# mcb-enhancer-v1.net
KiCad netlist of a schematic drawn in EAGLE
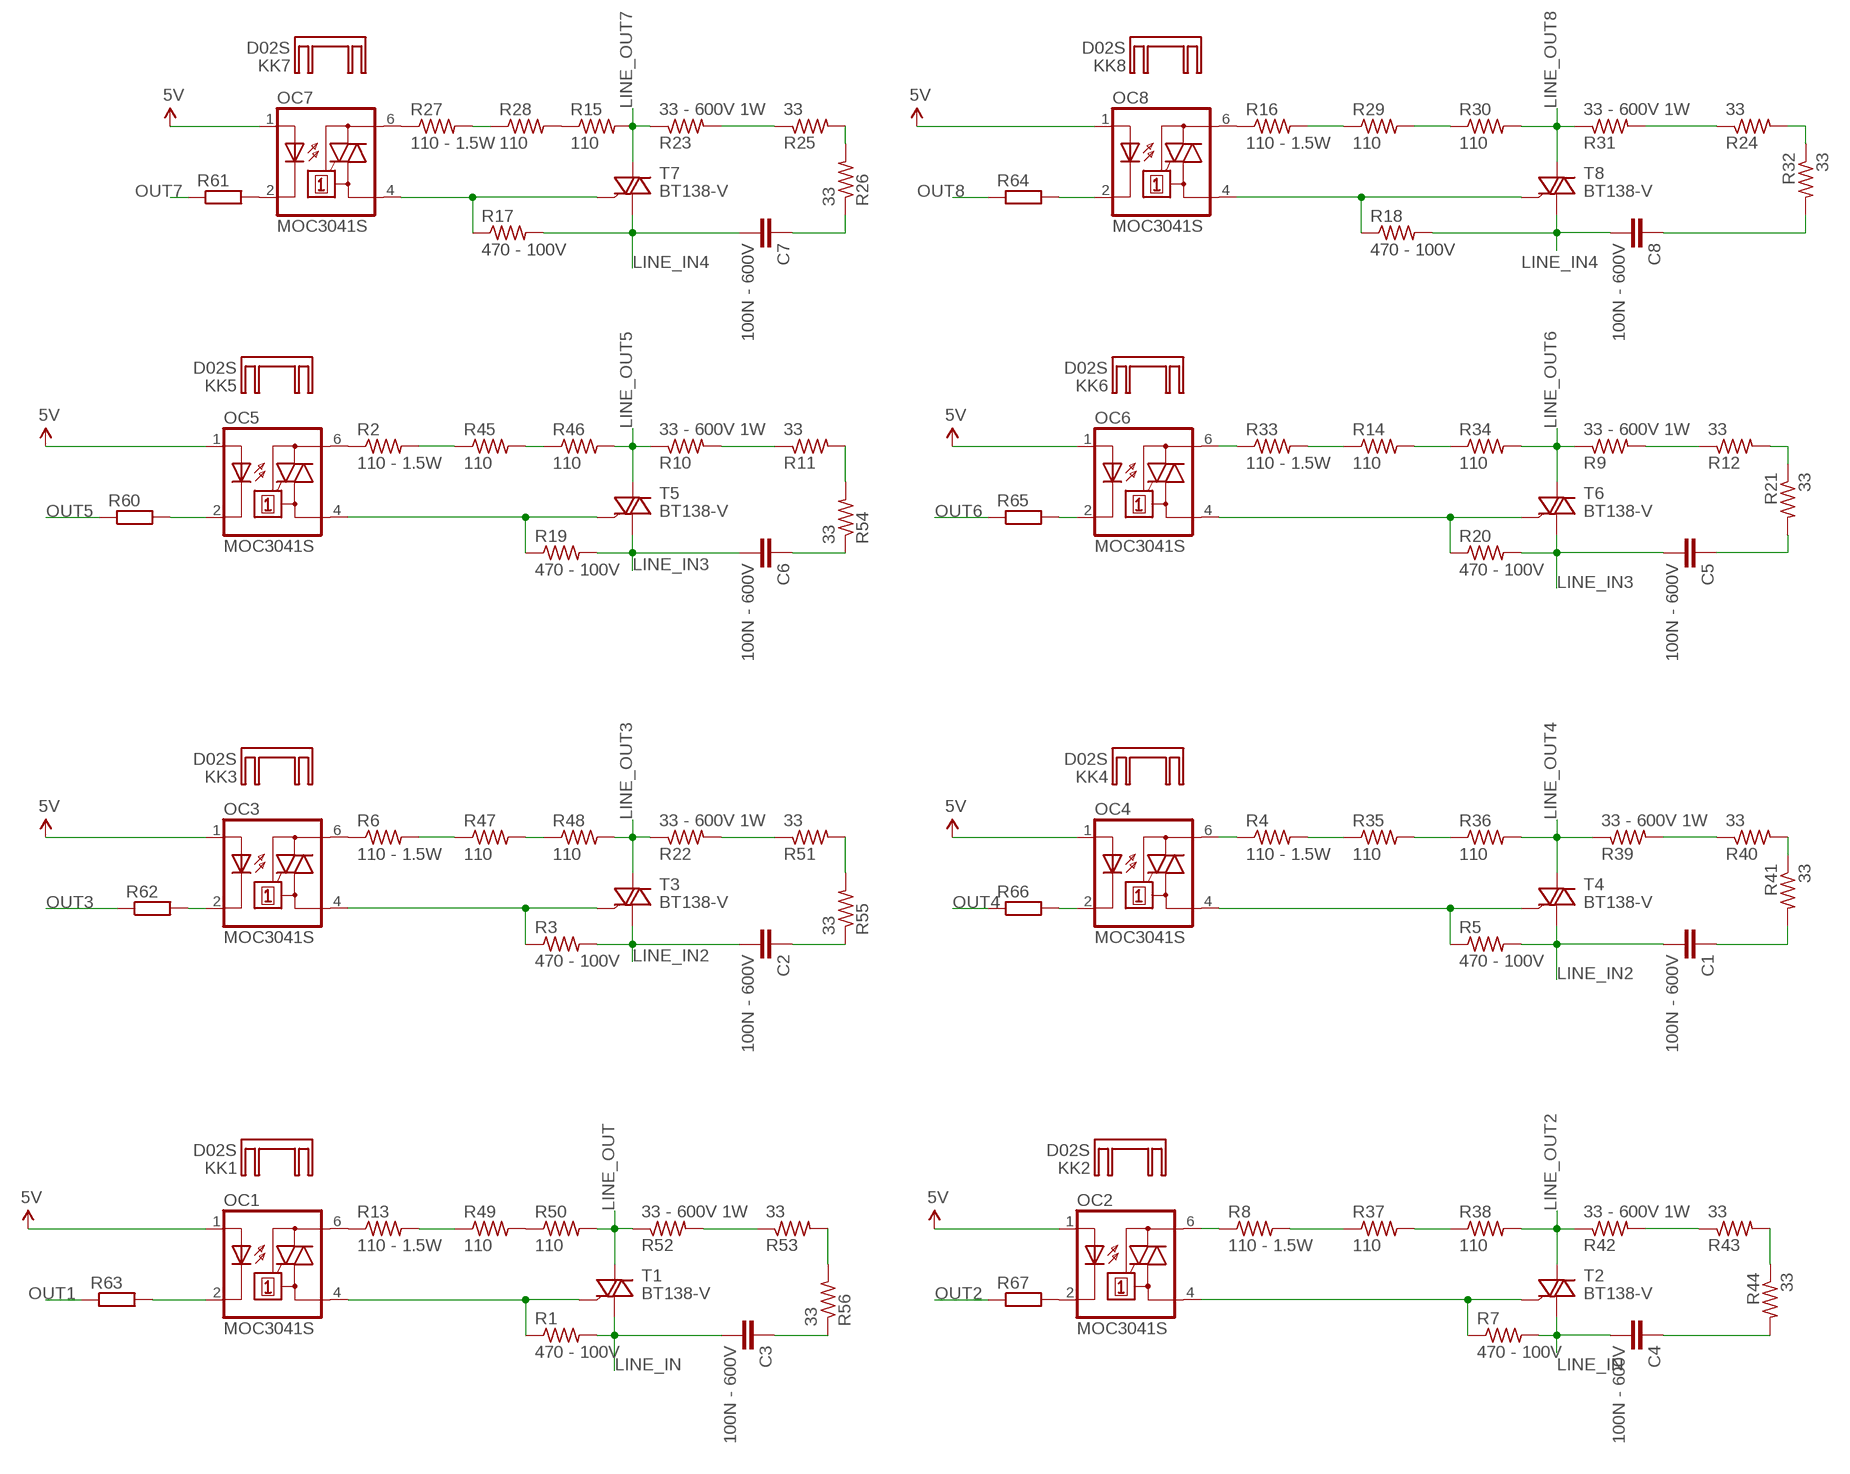
[diagram p0: schematic, sheet 1]

(export (version "E")
  (design (tool "Eeschema 10.0.6"))
  (components
    (comp (ref "C1")
      (value "100N - 600V")
      (footprint "eagle-import:C050-030X075")
      (libsource (lib "eagle-import") (part "C-EU050-030X075"))
    )
    (comp (ref "C2")
      (value "100N - 600V")
      (footprint "eagle-import:C050-030X075")
      (libsource (lib "eagle-import") (part "C-EU050-030X075"))
    )
    (comp (ref "C3")
      (value "100N - 600V")
      (footprint "eagle-import:C050-030X075")
      (libsource (lib "eagle-import") (part "C-EU050-030X075"))
    )
    (comp (ref "C4")
      (value "100N - 600V")
      (footprint "eagle-import:C050-030X075")
      (libsource (lib "eagle-import") (part "C-EU050-030X075"))
    )
    (comp (ref "C5")
      (value "100N - 600V")
      (footprint "eagle-import:C050-030X075")
      (libsource (lib "eagle-import") (part "C-EU050-030X075"))
    )
    (comp (ref "C6")
      (value "100N - 600V")
      (footprint "eagle-import:C050-030X075")
      (libsource (lib "eagle-import") (part "C-EU050-030X075"))
    )
    (comp (ref "C7")
      (value "100N - 600V")
      (footprint "eagle-import:C050-030X075")
      (libsource (lib "eagle-import") (part "C-EU050-030X075"))
    )
    (comp (ref "C8")
      (value "100N - 600V")
      (footprint "eagle-import:C050-030X075")
      (libsource (lib "eagle-import") (part "C-EU050-030X075"))
    )
    (comp (ref "KK1")
      (value "D02S")
      (footprint "eagle-import:D02S")
      (libsource (lib "eagle-import") (part "D02S"))
    )
    (comp (ref "KK2")
      (value "D02S")
      (footprint "eagle-import:D02S")
      (libsource (lib "eagle-import") (part "D02S"))
    )
    (comp (ref "KK3")
      (value "D02S")
      (footprint "eagle-import:D02S")
      (libsource (lib "eagle-import") (part "D02S"))
    )
    (comp (ref "KK4")
      (value "D02S")
      (footprint "eagle-import:D02S")
      (libsource (lib "eagle-import") (part "D02S"))
    )
    (comp (ref "KK5")
      (value "D02S")
      (footprint "eagle-import:D02S")
      (libsource (lib "eagle-import") (part "D02S"))
    )
    (comp (ref "KK6")
      (value "D02S")
      (footprint "eagle-import:D02S")
      (libsource (lib "eagle-import") (part "D02S"))
    )
    (comp (ref "KK7")
      (value "D02S")
      (footprint "eagle-import:D02S")
      (libsource (lib "eagle-import") (part "D02S"))
    )
    (comp (ref "KK8")
      (value "D02S")
      (footprint "eagle-import:D02S")
      (libsource (lib "eagle-import") (part "D02S"))
    )
    (comp (ref "OC1")
      (value "MOC3041S")
      (footprint "eagle-import:DIL6-SMD")
      (fields
        (field (name "MF") "FAIRCHILD SEMICONDUCTOR")
        (field (name "MPN") "MOC3041S-M")
        (field (name "MPN_1") "MOC3033S-M")
        (field (name "OC_FARNELL") "unknown")
        (field (name "OC_NEWARK") "05C2878")
      )
      (libsource (lib "eagle-import") (part "MOC30S41"))
    )
    (comp (ref "OC2")
      (value "MOC3041S")
      (footprint "eagle-import:DIL6-SMD")
      (fields
        (field (name "MF") "FAIRCHILD SEMICONDUCTOR")
        (field (name "MPN") "MOC3041S-M")
        (field (name "MPN_1") "MOC3033S-M")
        (field (name "OC_FARNELL") "unknown")
        (field (name "OC_NEWARK") "05C2878")
      )
      (libsource (lib "eagle-import") (part "MOC30S41"))
    )
    (comp (ref "OC3")
      (value "MOC3041S")
      (footprint "eagle-import:DIL6-SMD")
      (fields
        (field (name "MF") "FAIRCHILD SEMICONDUCTOR")
        (field (name "MPN") "MOC3041S-M")
        (field (name "MPN_1") "MOC3033S-M")
        (field (name "OC_FARNELL") "unknown")
        (field (name "OC_NEWARK") "05C2878")
      )
      (libsource (lib "eagle-import") (part "MOC30S41"))
    )
    (comp (ref "OC4")
      (value "MOC3041S")
      (footprint "eagle-import:DIL6-SMD")
      (fields
        (field (name "MF") "FAIRCHILD SEMICONDUCTOR")
        (field (name "MPN") "MOC3041S-M")
        (field (name "MPN_1") "MOC3033S-M")
        (field (name "OC_FARNELL") "unknown")
        (field (name "OC_NEWARK") "05C2878")
      )
      (libsource (lib "eagle-import") (part "MOC30S41"))
    )
    (comp (ref "OC5")
      (value "MOC3041S")
      (footprint "eagle-import:DIL6-SMD")
      (fields
        (field (name "MF") "FAIRCHILD SEMICONDUCTOR")
        (field (name "MPN") "MOC3041S-M")
        (field (name "MPN_1") "MOC3033S-M")
        (field (name "OC_FARNELL") "unknown")
        (field (name "OC_NEWARK") "05C2878")
      )
      (libsource (lib "eagle-import") (part "MOC30S41"))
    )
    (comp (ref "OC6")
      (value "MOC3041S")
      (footprint "eagle-import:DIL6-SMD")
      (fields
        (field (name "MF") "FAIRCHILD SEMICONDUCTOR")
        (field (name "MPN") "MOC3041S-M")
        (field (name "MPN_1") "MOC3033S-M")
        (field (name "OC_FARNELL") "unknown")
        (field (name "OC_NEWARK") "05C2878")
      )
      (libsource (lib "eagle-import") (part "MOC30S41"))
    )
    (comp (ref "OC7")
      (value "MOC3041S")
      (footprint "eagle-import:DIL6-SMD")
      (fields
        (field (name "MF") "FAIRCHILD SEMICONDUCTOR")
        (field (name "MPN") "MOC3041S-M")
        (field (name "MPN_1") "MOC3033S-M")
        (field (name "OC_FARNELL") "unknown")
        (field (name "OC_NEWARK") "05C2878")
      )
      (libsource (lib "eagle-import") (part "MOC30S41"))
    )
    (comp (ref "OC8")
      (value "MOC3041S")
      (footprint "eagle-import:DIL6-SMD")
      (fields
        (field (name "MF") "FAIRCHILD SEMICONDUCTOR")
        (field (name "MPN") "MOC3041S-M")
        (field (name "MPN_1") "MOC3033S-M")
        (field (name "OC_FARNELL") "unknown")
        (field (name "OC_NEWARK") "05C2878")
      )
      (libsource (lib "eagle-import") (part "MOC30S41"))
    )
    (comp (ref "R1")
      (value "470 - 100V")
      (footprint "eagle-import:M1206")
      (libsource (lib "eagle-import") (part "R-US_M1206"))
    )
    (comp (ref "R2")
      (value "110 - 1.5W")
      (footprint "eagle-import:R2512")
      (libsource (lib "eagle-import") (part "R-US_R2512"))
    )
    (comp (ref "R3")
      (value "470 - 100V")
      (footprint "eagle-import:M1206")
      (libsource (lib "eagle-import") (part "R-US_M1206"))
    )
    (comp (ref "R4")
      (value "110 - 1.5W")
      (footprint "eagle-import:R2512")
      (libsource (lib "eagle-import") (part "R-US_R2512"))
    )
    (comp (ref "R5")
      (value "470 - 100V")
      (footprint "eagle-import:M1206")
      (libsource (lib "eagle-import") (part "R-US_M1206"))
    )
    (comp (ref "R6")
      (value "110 - 1.5W")
      (footprint "eagle-import:R2512")
      (libsource (lib "eagle-import") (part "R-US_R2512"))
    )
    (comp (ref "R7")
      (value "470 - 100V")
      (footprint "eagle-import:M1206")
      (libsource (lib "eagle-import") (part "R-US_M1206"))
    )
    (comp (ref "R8")
      (value "110 - 1.5W")
      (footprint "eagle-import:R2512")
      (libsource (lib "eagle-import") (part "R-US_R2512"))
    )
    (comp (ref "R9")
      (value "33 - 600V 1W")
      (footprint "eagle-import:M1206")
      (libsource (lib "eagle-import") (part "R-US_M1206"))
    )
    (comp (ref "R10")
      (value "33 - 600V 1W")
      (footprint "eagle-import:M1206")
      (libsource (lib "eagle-import") (part "R-US_M1206"))
    )
    (comp (ref "R11")
      (value "33")
      (footprint "eagle-import:M1206")
      (libsource (lib "eagle-import") (part "R-US_M1206"))
    )
    (comp (ref "R12")
      (value "33")
      (footprint "eagle-import:M1206")
      (libsource (lib "eagle-import") (part "R-US_M1206"))
    )
    (comp (ref "R13")
      (value "110 - 1.5W")
      (footprint "eagle-import:R2512")
      (libsource (lib "eagle-import") (part "R-US_R2512"))
    )
    (comp (ref "R14")
      (value "110")
      (footprint "eagle-import:R2512")
      (libsource (lib "eagle-import") (part "R-US_R2512"))
    )
    (comp (ref "R15")
      (value "110")
      (footprint "eagle-import:R2512")
      (libsource (lib "eagle-import") (part "R-US_R2512"))
    )
    (comp (ref "R16")
      (value "110 - 1.5W")
      (footprint "eagle-import:R2512")
      (libsource (lib "eagle-import") (part "R-US_R2512"))
    )
    (comp (ref "R17")
      (value "470 - 100V")
      (footprint "eagle-import:M1206")
      (libsource (lib "eagle-import") (part "R-US_M1206"))
    )
    (comp (ref "R18")
      (value "470 - 100V")
      (footprint "eagle-import:M1206")
      (libsource (lib "eagle-import") (part "R-US_M1206"))
    )
    (comp (ref "R19")
      (value "470 - 100V")
      (footprint "eagle-import:M1206")
      (libsource (lib "eagle-import") (part "R-US_M1206"))
    )
    (comp (ref "R20")
      (value "470 - 100V")
      (footprint "eagle-import:M1206")
      (libsource (lib "eagle-import") (part "R-US_M1206"))
    )
    (comp (ref "R21")
      (value "33")
      (footprint "eagle-import:M1206")
      (libsource (lib "eagle-import") (part "R-US_M1206"))
    )
    (comp (ref "R22")
      (value "33 - 600V 1W")
      (footprint "eagle-import:M1206")
      (libsource (lib "eagle-import") (part "R-US_M1206"))
    )
    (comp (ref "R23")
      (value "33 - 600V 1W")
      (footprint "eagle-import:M1206")
      (libsource (lib "eagle-import") (part "R-US_M1206"))
    )
    (comp (ref "R24")
      (value "33")
      (footprint "eagle-import:M1206")
      (libsource (lib "eagle-import") (part "R-US_M1206"))
    )
    (comp (ref "R25")
      (value "33")
      (footprint "eagle-import:M1206")
      (libsource (lib "eagle-import") (part "R-US_M1206"))
    )
    (comp (ref "R26")
      (value "33")
      (footprint "eagle-import:M1206")
      (libsource (lib "eagle-import") (part "R-US_M1206"))
    )
    (comp (ref "R27")
      (value "110 - 1.5W")
      (footprint "eagle-import:R2512")
      (libsource (lib "eagle-import") (part "R-US_R2512"))
    )
    (comp (ref "R28")
      (value "110")
      (footprint "eagle-import:R2512")
      (libsource (lib "eagle-import") (part "R-US_R2512"))
    )
    (comp (ref "R29")
      (value "110")
      (footprint "eagle-import:R2512")
      (libsource (lib "eagle-import") (part "R-US_R2512"))
    )
    (comp (ref "R30")
      (value "110")
      (footprint "eagle-import:R2512")
      (libsource (lib "eagle-import") (part "R-US_R2512"))
    )
    (comp (ref "R31")
      (value "33 - 600V 1W")
      (footprint "eagle-import:M1206")
      (libsource (lib "eagle-import") (part "R-US_M1206"))
    )
    (comp (ref "R32")
      (value "33")
      (footprint "eagle-import:M1206")
      (libsource (lib "eagle-import") (part "R-US_M1206"))
    )
    (comp (ref "R33")
      (value "110 - 1.5W")
      (footprint "eagle-import:R2512")
      (libsource (lib "eagle-import") (part "R-US_R2512"))
    )
    (comp (ref "R34")
      (value "110")
      (footprint "eagle-import:R2512")
      (libsource (lib "eagle-import") (part "R-US_R2512"))
    )
    (comp (ref "R35")
      (value "110")
      (footprint "eagle-import:R2512")
      (libsource (lib "eagle-import") (part "R-US_R2512"))
    )
    (comp (ref "R36")
      (value "110")
      (footprint "eagle-import:R2512")
      (libsource (lib "eagle-import") (part "R-US_R2512"))
    )
    (comp (ref "R37")
      (value "110")
      (footprint "eagle-import:R2512")
      (libsource (lib "eagle-import") (part "R-US_R2512"))
    )
    (comp (ref "R38")
      (value "110")
      (footprint "eagle-import:R2512")
      (libsource (lib "eagle-import") (part "R-US_R2512"))
    )
    (comp (ref "R39")
      (value "33 - 600V 1W")
      (footprint "eagle-import:M1206")
      (libsource (lib "eagle-import") (part "R-US_M1206"))
    )
    (comp (ref "R40")
      (value "33")
      (footprint "eagle-import:M1206")
      (libsource (lib "eagle-import") (part "R-US_M1206"))
    )
    (comp (ref "R41")
      (value "33")
      (footprint "eagle-import:M1206")
      (libsource (lib "eagle-import") (part "R-US_M1206"))
    )
    (comp (ref "R42")
      (value "33 - 600V 1W")
      (footprint "eagle-import:M1206")
      (libsource (lib "eagle-import") (part "R-US_M1206"))
    )
    (comp (ref "R43")
      (value "33")
      (footprint "eagle-import:M1206")
      (libsource (lib "eagle-import") (part "R-US_M1206"))
    )
    (comp (ref "R44")
      (value "33")
      (footprint "eagle-import:M1206")
      (libsource (lib "eagle-import") (part "R-US_M1206"))
    )
    (comp (ref "R45")
      (value "110")
      (footprint "eagle-import:R2512")
      (libsource (lib "eagle-import") (part "R-US_R2512"))
    )
    (comp (ref "R46")
      (value "110")
      (footprint "eagle-import:R2512")
      (libsource (lib "eagle-import") (part "R-US_R2512"))
    )
    (comp (ref "R47")
      (value "110")
      (footprint "eagle-import:R2512")
      (libsource (lib "eagle-import") (part "R-US_R2512"))
    )
    (comp (ref "R48")
      (value "110")
      (footprint "eagle-import:R2512")
      (libsource (lib "eagle-import") (part "R-US_R2512"))
    )
    (comp (ref "R49")
      (value "110")
      (footprint "eagle-import:R2512")
      (libsource (lib "eagle-import") (part "R-US_R2512"))
    )
    (comp (ref "R50")
      (value "110")
      (footprint "eagle-import:R2512")
      (libsource (lib "eagle-import") (part "R-US_R2512"))
    )
    (comp (ref "R51")
      (value "33")
      (footprint "eagle-import:M1206")
      (libsource (lib "eagle-import") (part "R-US_M1206"))
    )
    (comp (ref "R52")
      (value "33 - 600V 1W")
      (footprint "eagle-import:M1206")
      (libsource (lib "eagle-import") (part "R-US_M1206"))
    )
    (comp (ref "R53")
      (value "33")
      (footprint "eagle-import:M1206")
      (libsource (lib "eagle-import") (part "R-US_M1206"))
    )
    (comp (ref "R54")
      (value "33")
      (footprint "eagle-import:M1206")
      (libsource (lib "eagle-import") (part "R-US_M1206"))
    )
    (comp (ref "R55")
      (value "33")
      (footprint "eagle-import:M1206")
      (libsource (lib "eagle-import") (part "R-US_M1206"))
    )
    (comp (ref "R56")
      (value "33")
      (footprint "eagle-import:M1206")
      (libsource (lib "eagle-import") (part "R-US_M1206"))
    )
    (comp (ref "R60")
      (value "R-EU_R0603")
      (footprint "eagle-import:R0603")
      (libsource (lib "eagle-import") (part "R-EU_R0603"))
    )
    (comp (ref "R61")
      (value "R-EU_R0603")
      (footprint "eagle-import:R0603")
      (libsource (lib "eagle-import") (part "R-EU_R0603"))
    )
    (comp (ref "R62")
      (value "R-EU_R0603")
      (footprint "eagle-import:R0603")
      (libsource (lib "eagle-import") (part "R-EU_R0603"))
    )
    (comp (ref "R63")
      (value "R-EU_R0603")
      (footprint "eagle-import:R0603")
      (libsource (lib "eagle-import") (part "R-EU_R0603"))
    )
    (comp (ref "R64")
      (value "R-EU_R0603")
      (footprint "eagle-import:R0603")
      (libsource (lib "eagle-import") (part "R-EU_R0603"))
    )
    (comp (ref "R65")
      (value "R-EU_R0603")
      (footprint "eagle-import:R0603")
      (libsource (lib "eagle-import") (part "R-EU_R0603"))
    )
    (comp (ref "R66")
      (value "R-EU_R0603")
      (footprint "eagle-import:R0603")
      (libsource (lib "eagle-import") (part "R-EU_R0603"))
    )
    (comp (ref "R67")
      (value "R-EU_R0603")
      (footprint "eagle-import:R0603")
      (libsource (lib "eagle-import") (part "R-EU_R0603"))
    )
    (comp (ref "T1")
      (value "BT138-V")
      (footprint "eagle-import:TO220BV")
      (libsource (lib "eagle-import") (part "BT138-V"))
    )
    (comp (ref "T2")
      (value "BT138-V")
      (footprint "eagle-import:TO220BV")
      (libsource (lib "eagle-import") (part "BT138-V"))
    )
    (comp (ref "T3")
      (value "BT138-V")
      (footprint "eagle-import:TO220BV")
      (libsource (lib "eagle-import") (part "BT138-V"))
    )
    (comp (ref "T4")
      (value "BT138-V")
      (footprint "eagle-import:TO220BV")
      (libsource (lib "eagle-import") (part "BT138-V"))
    )
    (comp (ref "T5")
      (value "BT138-V")
      (footprint "eagle-import:TO220BV")
      (libsource (lib "eagle-import") (part "BT138-V"))
    )
    (comp (ref "T6")
      (value "BT138-V")
      (footprint "eagle-import:TO220BV")
      (libsource (lib "eagle-import") (part "BT138-V"))
    )
    (comp (ref "T7")
      (value "BT138-V")
      (footprint "eagle-import:TO220BV")
      (libsource (lib "eagle-import") (part "BT138-V"))
    )
    (comp (ref "T8")
      (value "BT138-V")
      (footprint "eagle-import:TO220BV")
      (libsource (lib "eagle-import") (part "BT138-V"))
    )
  )
  (nets
    (net (code "1") (name "/LINE_IN") (class "Default")
      (node (ref "C3") (pin "2") (pinfunction "2_2") (pintype "passive"))
      (node (ref "C4") (pin "2") (pinfunction "2_2") (pintype "passive"))
      (node (ref "R1") (pin "2") (pinfunction "2_2") (pintype "passive"))
      (node (ref "R7") (pin "2") (pinfunction "2_2") (pintype "passive"))
      (node (ref "T1") (pin "T1") (pinfunction "A1_T1") (pintype "passive"))
      (node (ref "T2") (pin "T1") (pinfunction "A1_T1") (pintype "passive"))
    )
    (net (code "2") (name "/LINE_IN2") (class "Default")
      (node (ref "C1") (pin "2") (pinfunction "2_2") (pintype "passive"))
      (node (ref "C2") (pin "2") (pinfunction "2_2") (pintype "passive"))
      (node (ref "R3") (pin "2") (pinfunction "2_2") (pintype "passive"))
      (node (ref "R5") (pin "2") (pinfunction "2_2") (pintype "passive"))
      (node (ref "T3") (pin "T1") (pinfunction "A1_T1") (pintype "passive"))
      (node (ref "T4") (pin "T1") (pinfunction "A1_T1") (pintype "passive"))
    )
    (net (code "3") (name "/LINE_IN3") (class "Default")
      (node (ref "C5") (pin "2") (pinfunction "2_2") (pintype "passive"))
      (node (ref "C6") (pin "2") (pinfunction "2_2") (pintype "passive"))
      (node (ref "R19") (pin "2") (pinfunction "2_2") (pintype "passive"))
      (node (ref "R20") (pin "2") (pinfunction "2_2") (pintype "passive"))
      (node (ref "T5") (pin "T1") (pinfunction "A1_T1") (pintype "passive"))
      (node (ref "T6") (pin "T1") (pinfunction "A1_T1") (pintype "passive"))
    )
    (net (code "4") (name "/LINE_IN4") (class "Default")
      (node (ref "C7") (pin "2") (pinfunction "2_2") (pintype "passive"))
      (node (ref "C8") (pin "2") (pinfunction "2_2") (pintype "passive"))
      (node (ref "R17") (pin "2") (pinfunction "2_2") (pintype "passive"))
      (node (ref "R18") (pin "2") (pinfunction "2_2") (pintype "passive"))
      (node (ref "T7") (pin "T1") (pinfunction "A1_T1") (pintype "passive"))
      (node (ref "T8") (pin "T1") (pinfunction "A1_T1") (pintype "passive"))
    )
    (net (code "5") (name "/LINE_OUT") (class "Default")
      (node (ref "R50") (pin "2") (pinfunction "2_2") (pintype "passive"))
      (node (ref "R52") (pin "1") (pinfunction "1_1") (pintype "passive"))
      (node (ref "T1") (pin "T2") (pinfunction "A2_T2") (pintype "passive"))
    )
    (net (code "6") (name "/LINE_OUT2") (class "Default")
      (node (ref "R38") (pin "2") (pinfunction "2_2") (pintype "passive"))
      (node (ref "R42") (pin "1") (pinfunction "1_1") (pintype "passive"))
      (node (ref "T2") (pin "T2") (pinfunction "A2_T2") (pintype "passive"))
    )
    (net (code "7") (name "/LINE_OUT3") (class "Default")
      (node (ref "R22") (pin "1") (pinfunction "1_1") (pintype "passive"))
      (node (ref "R48") (pin "2") (pinfunction "2_2") (pintype "passive"))
      (node (ref "T3") (pin "T2") (pinfunction "A2_T2") (pintype "passive"))
    )
    (net (code "8") (name "/LINE_OUT4") (class "Default")
      (node (ref "R36") (pin "2") (pinfunction "2_2") (pintype "passive"))
      (node (ref "R39") (pin "1") (pinfunction "1_1") (pintype "passive"))
      (node (ref "T4") (pin "T2") (pinfunction "A2_T2") (pintype "passive"))
    )
    (net (code "9") (name "/LINE_OUT5") (class "Default")
      (node (ref "R10") (pin "1") (pinfunction "1_1") (pintype "passive"))
      (node (ref "R46") (pin "2") (pinfunction "2_2") (pintype "passive"))
      (node (ref "T5") (pin "T2") (pinfunction "A2_T2") (pintype "passive"))
    )
    (net (code "10") (name "/LINE_OUT6") (class "Default")
      (node (ref "R34") (pin "2") (pinfunction "2_2") (pintype "passive"))
      (node (ref "R9") (pin "1") (pinfunction "1_1") (pintype "passive"))
      (node (ref "T6") (pin "T2") (pinfunction "A2_T2") (pintype "passive"))
    )
    (net (code "11") (name "/LINE_OUT7") (class "Default")
      (node (ref "R15") (pin "2") (pinfunction "2_2") (pintype "passive"))
      (node (ref "R23") (pin "1") (pinfunction "1_1") (pintype "passive"))
      (node (ref "T7") (pin "T2") (pinfunction "A2_T2") (pintype "passive"))
    )
    (net (code "12") (name "/LINE_OUT8") (class "Default")
      (node (ref "R30") (pin "2") (pinfunction "2_2") (pintype "passive"))
      (node (ref "R31") (pin "1") (pinfunction "1_1") (pintype "passive"))
      (node (ref "T8") (pin "T2") (pinfunction "A2_T2") (pintype "passive"))
    )
    (net (code "13") (name "/OUT1") (class "Default")
      (node (ref "R63") (pin "1") (pinfunction "1_1") (pintype "passive"))
    )
    (net (code "14") (name "/OUT2") (class "Default")
      (node (ref "R67") (pin "1") (pinfunction "1_1") (pintype "passive"))
    )
    (net (code "15") (name "/OUT3") (class "Default")
      (node (ref "R62") (pin "1") (pinfunction "1_1") (pintype "passive"))
    )
    (net (code "16") (name "/OUT4") (class "Default")
      (node (ref "R66") (pin "1") (pinfunction "1_1") (pintype "passive"))
    )
    (net (code "17") (name "/OUT5") (class "Default")
      (node (ref "R60") (pin "1") (pinfunction "1_1") (pintype "passive"))
    )
    (net (code "18") (name "/OUT6") (class "Default")
      (node (ref "R65") (pin "1") (pinfunction "1_1") (pintype "passive"))
    )
    (net (code "19") (name "/OUT7") (class "Default")
      (node (ref "R61") (pin "1") (pinfunction "1_1") (pintype "passive"))
    )
    (net (code "20") (name "/OUT8") (class "Default")
      (node (ref "R64") (pin "1") (pinfunction "1_1") (pintype "passive"))
    )
    (net (code "21") (name "5V") (class "Default")
      (node (ref "OC1") (pin "1") (pinfunction "A_1") (pintype "passive"))
      (node (ref "OC2") (pin "1") (pinfunction "A_1") (pintype "passive"))
      (node (ref "OC3") (pin "1") (pinfunction "A_1") (pintype "passive"))
      (node (ref "OC4") (pin "1") (pinfunction "A_1") (pintype "passive"))
      (node (ref "OC5") (pin "1") (pinfunction "A_1") (pintype "passive"))
      (node (ref "OC6") (pin "1") (pinfunction "A_1") (pintype "passive"))
      (node (ref "OC7") (pin "1") (pinfunction "A_1") (pintype "passive"))
      (node (ref "OC8") (pin "1") (pinfunction "A_1") (pintype "passive"))
    )
    (net (code "22") (name "Net-(C1-Pad1)") (class "Default")
      (node (ref "C1") (pin "1") (pinfunction "1_1") (pintype "passive"))
      (node (ref "R41") (pin "2") (pinfunction "2_2") (pintype "passive"))
    )
    (net (code "23") (name "Net-(C2-Pad1)") (class "Default")
      (node (ref "C2") (pin "1") (pinfunction "1_1") (pintype "passive"))
      (node (ref "R55") (pin "1") (pinfunction "1_1") (pintype "passive"))
    )
    (net (code "24") (name "Net-(C3-Pad1)") (class "Default")
      (node (ref "C3") (pin "1") (pinfunction "1_1") (pintype "passive"))
      (node (ref "R56") (pin "1") (pinfunction "1_1") (pintype "passive"))
    )
    (net (code "25") (name "Net-(C4-Pad1)") (class "Default")
      (node (ref "C4") (pin "1") (pinfunction "1_1") (pintype "passive"))
      (node (ref "R44") (pin "2") (pinfunction "2_2") (pintype "passive"))
    )
    (net (code "26") (name "Net-(C5-Pad1)") (class "Default")
      (node (ref "C5") (pin "1") (pinfunction "1_1") (pintype "passive"))
      (node (ref "R21") (pin "2") (pinfunction "2_2") (pintype "passive"))
    )
    (net (code "27") (name "Net-(C6-Pad1)") (class "Default")
      (node (ref "C6") (pin "1") (pinfunction "1_1") (pintype "passive"))
      (node (ref "R54") (pin "1") (pinfunction "1_1") (pintype "passive"))
    )
    (net (code "28") (name "Net-(C7-Pad1)") (class "Default")
      (node (ref "C7") (pin "1") (pinfunction "1_1") (pintype "passive"))
      (node (ref "R26") (pin "1") (pinfunction "1_1") (pintype "passive"))
    )
    (net (code "29") (name "Net-(C8-Pad1)") (class "Default")
      (node (ref "C8") (pin "1") (pinfunction "1_1") (pintype "passive"))
      (node (ref "R32") (pin "2") (pinfunction "2_2") (pintype "passive"))
    )
    (net (code "30") (name "Net-(OC1-A1)") (class "Default")
      (node (ref "OC1") (pin "4") (pinfunction "A1_4") (pintype "passive"))
      (node (ref "R1") (pin "1") (pinfunction "1_1") (pintype "passive"))
      (node (ref "T1") (pin "G") (pinfunction "G_G") (pintype "passive"))
    )
    (net (code "31") (name "Net-(OC1-A2)") (class "Default")
      (node (ref "OC1") (pin "6") (pinfunction "A2_6") (pintype "passive"))
      (node (ref "R13") (pin "1") (pinfunction "1_1") (pintype "passive"))
    )
    (net (code "32") (name "Net-(OC1-C)") (class "Default")
      (node (ref "OC1") (pin "2") (pinfunction "C_2") (pintype "passive"))
      (node (ref "R63") (pin "2") (pinfunction "2_2") (pintype "passive"))
    )
    (net (code "33") (name "Net-(OC2-A1)") (class "Default")
      (node (ref "OC2") (pin "4") (pinfunction "A1_4") (pintype "passive"))
      (node (ref "R7") (pin "1") (pinfunction "1_1") (pintype "passive"))
      (node (ref "T2") (pin "G") (pinfunction "G_G") (pintype "passive"))
    )
    (net (code "34") (name "Net-(OC2-A2)") (class "Default")
      (node (ref "OC2") (pin "6") (pinfunction "A2_6") (pintype "passive"))
      (node (ref "R8") (pin "1") (pinfunction "1_1") (pintype "passive"))
    )
    (net (code "35") (name "Net-(OC2-C)") (class "Default")
      (node (ref "OC2") (pin "2") (pinfunction "C_2") (pintype "passive"))
      (node (ref "R67") (pin "2") (pinfunction "2_2") (pintype "passive"))
    )
    (net (code "36") (name "Net-(OC3-A1)") (class "Default")
      (node (ref "OC3") (pin "4") (pinfunction "A1_4") (pintype "passive"))
      (node (ref "R3") (pin "1") (pinfunction "1_1") (pintype "passive"))
      (node (ref "T3") (pin "G") (pinfunction "G_G") (pintype "passive"))
    )
    (net (code "37") (name "Net-(OC3-A2)") (class "Default")
      (node (ref "OC3") (pin "6") (pinfunction "A2_6") (pintype "passive"))
      (node (ref "R6") (pin "1") (pinfunction "1_1") (pintype "passive"))
    )
    (net (code "38") (name "Net-(OC3-C)") (class "Default")
      (node (ref "OC3") (pin "2") (pinfunction "C_2") (pintype "passive"))
      (node (ref "R62") (pin "2") (pinfunction "2_2") (pintype "passive"))
    )
    (net (code "39") (name "Net-(OC4-A1)") (class "Default")
      (node (ref "OC4") (pin "4") (pinfunction "A1_4") (pintype "passive"))
      (node (ref "R5") (pin "1") (pinfunction "1_1") (pintype "passive"))
      (node (ref "T4") (pin "G") (pinfunction "G_G") (pintype "passive"))
    )
    (net (code "40") (name "Net-(OC4-A2)") (class "Default")
      (node (ref "OC4") (pin "6") (pinfunction "A2_6") (pintype "passive"))
      (node (ref "R4") (pin "1") (pinfunction "1_1") (pintype "passive"))
    )
    (net (code "41") (name "Net-(OC4-C)") (class "Default")
      (node (ref "OC4") (pin "2") (pinfunction "C_2") (pintype "passive"))
      (node (ref "R66") (pin "2") (pinfunction "2_2") (pintype "passive"))
    )
    (net (code "42") (name "Net-(OC5-A1)") (class "Default")
      (node (ref "OC5") (pin "4") (pinfunction "A1_4") (pintype "passive"))
      (node (ref "R19") (pin "1") (pinfunction "1_1") (pintype "passive"))
      (node (ref "T5") (pin "G") (pinfunction "G_G") (pintype "passive"))
    )
    (net (code "43") (name "Net-(OC5-A2)") (class "Default")
      (node (ref "OC5") (pin "6") (pinfunction "A2_6") (pintype "passive"))
      (node (ref "R2") (pin "1") (pinfunction "1_1") (pintype "passive"))
    )
    (net (code "44") (name "Net-(OC5-C)") (class "Default")
      (node (ref "OC5") (pin "2") (pinfunction "C_2") (pintype "passive"))
      (node (ref "R60") (pin "2") (pinfunction "2_2") (pintype "passive"))
    )
    (net (code "45") (name "Net-(OC6-A1)") (class "Default")
      (node (ref "OC6") (pin "4") (pinfunction "A1_4") (pintype "passive"))
      (node (ref "R20") (pin "1") (pinfunction "1_1") (pintype "passive"))
      (node (ref "T6") (pin "G") (pinfunction "G_G") (pintype "passive"))
    )
    (net (code "46") (name "Net-(OC6-A2)") (class "Default")
      (node (ref "OC6") (pin "6") (pinfunction "A2_6") (pintype "passive"))
      (node (ref "R33") (pin "1") (pinfunction "1_1") (pintype "passive"))
    )
    (net (code "47") (name "Net-(OC6-C)") (class "Default")
      (node (ref "OC6") (pin "2") (pinfunction "C_2") (pintype "passive"))
      (node (ref "R65") (pin "2") (pinfunction "2_2") (pintype "passive"))
    )
    (net (code "48") (name "Net-(OC7-A1)") (class "Default")
      (node (ref "OC7") (pin "4") (pinfunction "A1_4") (pintype "passive"))
      (node (ref "R17") (pin "1") (pinfunction "1_1") (pintype "passive"))
      (node (ref "T7") (pin "G") (pinfunction "G_G") (pintype "passive"))
    )
    (net (code "49") (name "Net-(OC7-A2)") (class "Default")
      (node (ref "OC7") (pin "6") (pinfunction "A2_6") (pintype "passive"))
      (node (ref "R27") (pin "1") (pinfunction "1_1") (pintype "passive"))
    )
    (net (code "50") (name "Net-(OC7-C)") (class "Default")
      (node (ref "OC7") (pin "2") (pinfunction "C_2") (pintype "passive"))
      (node (ref "R61") (pin "2") (pinfunction "2_2") (pintype "passive"))
    )
    (net (code "51") (name "Net-(OC8-A1)") (class "Default")
      (node (ref "OC8") (pin "4") (pinfunction "A1_4") (pintype "passive"))
      (node (ref "R18") (pin "1") (pinfunction "1_1") (pintype "passive"))
      (node (ref "T8") (pin "G") (pinfunction "G_G") (pintype "passive"))
    )
    (net (code "52") (name "Net-(OC8-A2)") (class "Default")
      (node (ref "OC8") (pin "6") (pinfunction "A2_6") (pintype "passive"))
      (node (ref "R16") (pin "1") (pinfunction "1_1") (pintype "passive"))
    )
    (net (code "53") (name "Net-(OC8-C)") (class "Default")
      (node (ref "OC8") (pin "2") (pinfunction "C_2") (pintype "passive"))
      (node (ref "R64") (pin "2") (pinfunction "2_2") (pintype "passive"))
    )
    (net (code "54") (name "Net-(R2-Pad2)") (class "Default")
      (node (ref "R2") (pin "2") (pinfunction "2_2") (pintype "passive"))
      (node (ref "R45") (pin "1") (pinfunction "1_1") (pintype "passive"))
    )
    (net (code "55") (name "Net-(R10-Pad2)") (class "Default")
      (node (ref "R10") (pin "2") (pinfunction "2_2") (pintype "passive"))
      (node (ref "R11") (pin "1") (pinfunction "1_1") (pintype "passive"))
    )
    (net (code "56") (name "Net-(R11-Pad2)") (class "Default")
      (node (ref "R11") (pin "2") (pinfunction "2_2") (pintype "passive"))
      (node (ref "R54") (pin "2") (pinfunction "2_2") (pintype "passive"))
    )
    (net (code "57") (name "Net-(R12-Pad1)") (class "Default")
      (node (ref "R12") (pin "1") (pinfunction "1_1") (pintype "passive"))
      (node (ref "R9") (pin "2") (pinfunction "2_2") (pintype "passive"))
    )
    (net (code "58") (name "Net-(R12-Pad2)") (class "Default")
      (node (ref "R12") (pin "2") (pinfunction "2_2") (pintype "passive"))
      (node (ref "R21") (pin "1") (pinfunction "1_1") (pintype "passive"))
    )
    (net (code "59") (name "Net-(R13-Pad2)") (class "Default")
      (node (ref "R13") (pin "2") (pinfunction "2_2") (pintype "passive"))
      (node (ref "R49") (pin "1") (pinfunction "1_1") (pintype "passive"))
    )
    (net (code "60") (name "Net-(R14-Pad1)") (class "Default")
      (node (ref "R14") (pin "1") (pinfunction "1_1") (pintype "passive"))
      (node (ref "R33") (pin "2") (pinfunction "2_2") (pintype "passive"))
    )
    (net (code "61") (name "Net-(R14-Pad2)") (class "Default")
      (node (ref "R14") (pin "2") (pinfunction "2_2") (pintype "passive"))
      (node (ref "R34") (pin "1") (pinfunction "1_1") (pintype "passive"))
    )
    (net (code "62") (name "Net-(R15-Pad1)") (class "Default")
      (node (ref "R15") (pin "1") (pinfunction "1_1") (pintype "passive"))
      (node (ref "R28") (pin "2") (pinfunction "2_2") (pintype "passive"))
    )
    (net (code "63") (name "Net-(R16-Pad2)") (class "Default")
      (node (ref "R16") (pin "2") (pinfunction "2_2") (pintype "passive"))
      (node (ref "R29") (pin "1") (pinfunction "1_1") (pintype "passive"))
    )
    (net (code "64") (name "Net-(R22-Pad2)") (class "Default")
      (node (ref "R22") (pin "2") (pinfunction "2_2") (pintype "passive"))
      (node (ref "R51") (pin "1") (pinfunction "1_1") (pintype "passive"))
    )
    (net (code "65") (name "Net-(R23-Pad2)") (class "Default")
      (node (ref "R23") (pin "2") (pinfunction "2_2") (pintype "passive"))
      (node (ref "R25") (pin "1") (pinfunction "1_1") (pintype "passive"))
    )
    (net (code "66") (name "Net-(R24-Pad1)") (class "Default")
      (node (ref "R24") (pin "1") (pinfunction "1_1") (pintype "passive"))
      (node (ref "R31") (pin "2") (pinfunction "2_2") (pintype "passive"))
    )
    (net (code "67") (name "Net-(R24-Pad2)") (class "Default")
      (node (ref "R24") (pin "2") (pinfunction "2_2") (pintype "passive"))
      (node (ref "R32") (pin "1") (pinfunction "1_1") (pintype "passive"))
    )
    (net (code "68") (name "Net-(R25-Pad2)") (class "Default")
      (node (ref "R25") (pin "2") (pinfunction "2_2") (pintype "passive"))
      (node (ref "R26") (pin "2") (pinfunction "2_2") (pintype "passive"))
    )
    (net (code "69") (name "Net-(R27-Pad2)") (class "Default")
      (node (ref "R27") (pin "2") (pinfunction "2_2") (pintype "passive"))
      (node (ref "R28") (pin "1") (pinfunction "1_1") (pintype "passive"))
    )
    (net (code "70") (name "Net-(R29-Pad2)") (class "Default")
      (node (ref "R29") (pin "2") (pinfunction "2_2") (pintype "passive"))
      (node (ref "R30") (pin "1") (pinfunction "1_1") (pintype "passive"))
    )
    (net (code "71") (name "Net-(R35-Pad1)") (class "Default")
      (node (ref "R35") (pin "1") (pinfunction "1_1") (pintype "passive"))
      (node (ref "R4") (pin "2") (pinfunction "2_2") (pintype "passive"))
    )
    (net (code "72") (name "Net-(R35-Pad2)") (class "Default")
      (node (ref "R35") (pin "2") (pinfunction "2_2") (pintype "passive"))
      (node (ref "R36") (pin "1") (pinfunction "1_1") (pintype "passive"))
    )
    (net (code "73") (name "Net-(R37-Pad1)") (class "Default")
      (node (ref "R37") (pin "1") (pinfunction "1_1") (pintype "passive"))
      (node (ref "R8") (pin "2") (pinfunction "2_2") (pintype "passive"))
    )
    (net (code "74") (name "Net-(R37-Pad2)") (class "Default")
      (node (ref "R37") (pin "2") (pinfunction "2_2") (pintype "passive"))
      (node (ref "R38") (pin "1") (pinfunction "1_1") (pintype "passive"))
    )
    (net (code "75") (name "Net-(R39-Pad2)") (class "Default")
      (node (ref "R39") (pin "2") (pinfunction "2_2") (pintype "passive"))
      (node (ref "R40") (pin "1") (pinfunction "1_1") (pintype "passive"))
    )
    (net (code "76") (name "Net-(R40-Pad2)") (class "Default")
      (node (ref "R40") (pin "2") (pinfunction "2_2") (pintype "passive"))
      (node (ref "R41") (pin "1") (pinfunction "1_1") (pintype "passive"))
    )
    (net (code "77") (name "Net-(R42-Pad2)") (class "Default")
      (node (ref "R42") (pin "2") (pinfunction "2_2") (pintype "passive"))
      (node (ref "R43") (pin "1") (pinfunction "1_1") (pintype "passive"))
    )
    (net (code "78") (name "Net-(R43-Pad2)") (class "Default")
      (node (ref "R43") (pin "2") (pinfunction "2_2") (pintype "passive"))
      (node (ref "R44") (pin "1") (pinfunction "1_1") (pintype "passive"))
    )
    (net (code "79") (name "Net-(R45-Pad2)") (class "Default")
      (node (ref "R45") (pin "2") (pinfunction "2_2") (pintype "passive"))
      (node (ref "R46") (pin "1") (pinfunction "1_1") (pintype "passive"))
    )
    (net (code "80") (name "Net-(R47-Pad1)") (class "Default")
      (node (ref "R47") (pin "1") (pinfunction "1_1") (pintype "passive"))
      (node (ref "R6") (pin "2") (pinfunction "2_2") (pintype "passive"))
    )
    (net (code "81") (name "Net-(R47-Pad2)") (class "Default")
      (node (ref "R47") (pin "2") (pinfunction "2_2") (pintype "passive"))
      (node (ref "R48") (pin "1") (pinfunction "1_1") (pintype "passive"))
    )
    (net (code "82") (name "Net-(R49-Pad2)") (class "Default")
      (node (ref "R49") (pin "2") (pinfunction "2_2") (pintype "passive"))
      (node (ref "R50") (pin "1") (pinfunction "1_1") (pintype "passive"))
    )
    (net (code "83") (name "Net-(R51-Pad2)") (class "Default")
      (node (ref "R51") (pin "2") (pinfunction "2_2") (pintype "passive"))
      (node (ref "R55") (pin "2") (pinfunction "2_2") (pintype "passive"))
    )
    (net (code "84") (name "Net-(R52-Pad2)") (class "Default")
      (node (ref "R52") (pin "2") (pinfunction "2_2") (pintype "passive"))
      (node (ref "R53") (pin "1") (pinfunction "1_1") (pintype "passive"))
    )
    (net (code "85") (name "Net-(R53-Pad2)") (class "Default")
      (node (ref "R53") (pin "2") (pinfunction "2_2") (pintype "passive"))
      (node (ref "R56") (pin "2") (pinfunction "2_2") (pintype "passive"))
    )
  )
)
